# KineticHarvester_SIG_UFL_5.net
KiCad netlist of a schematic drawn in EAGLE
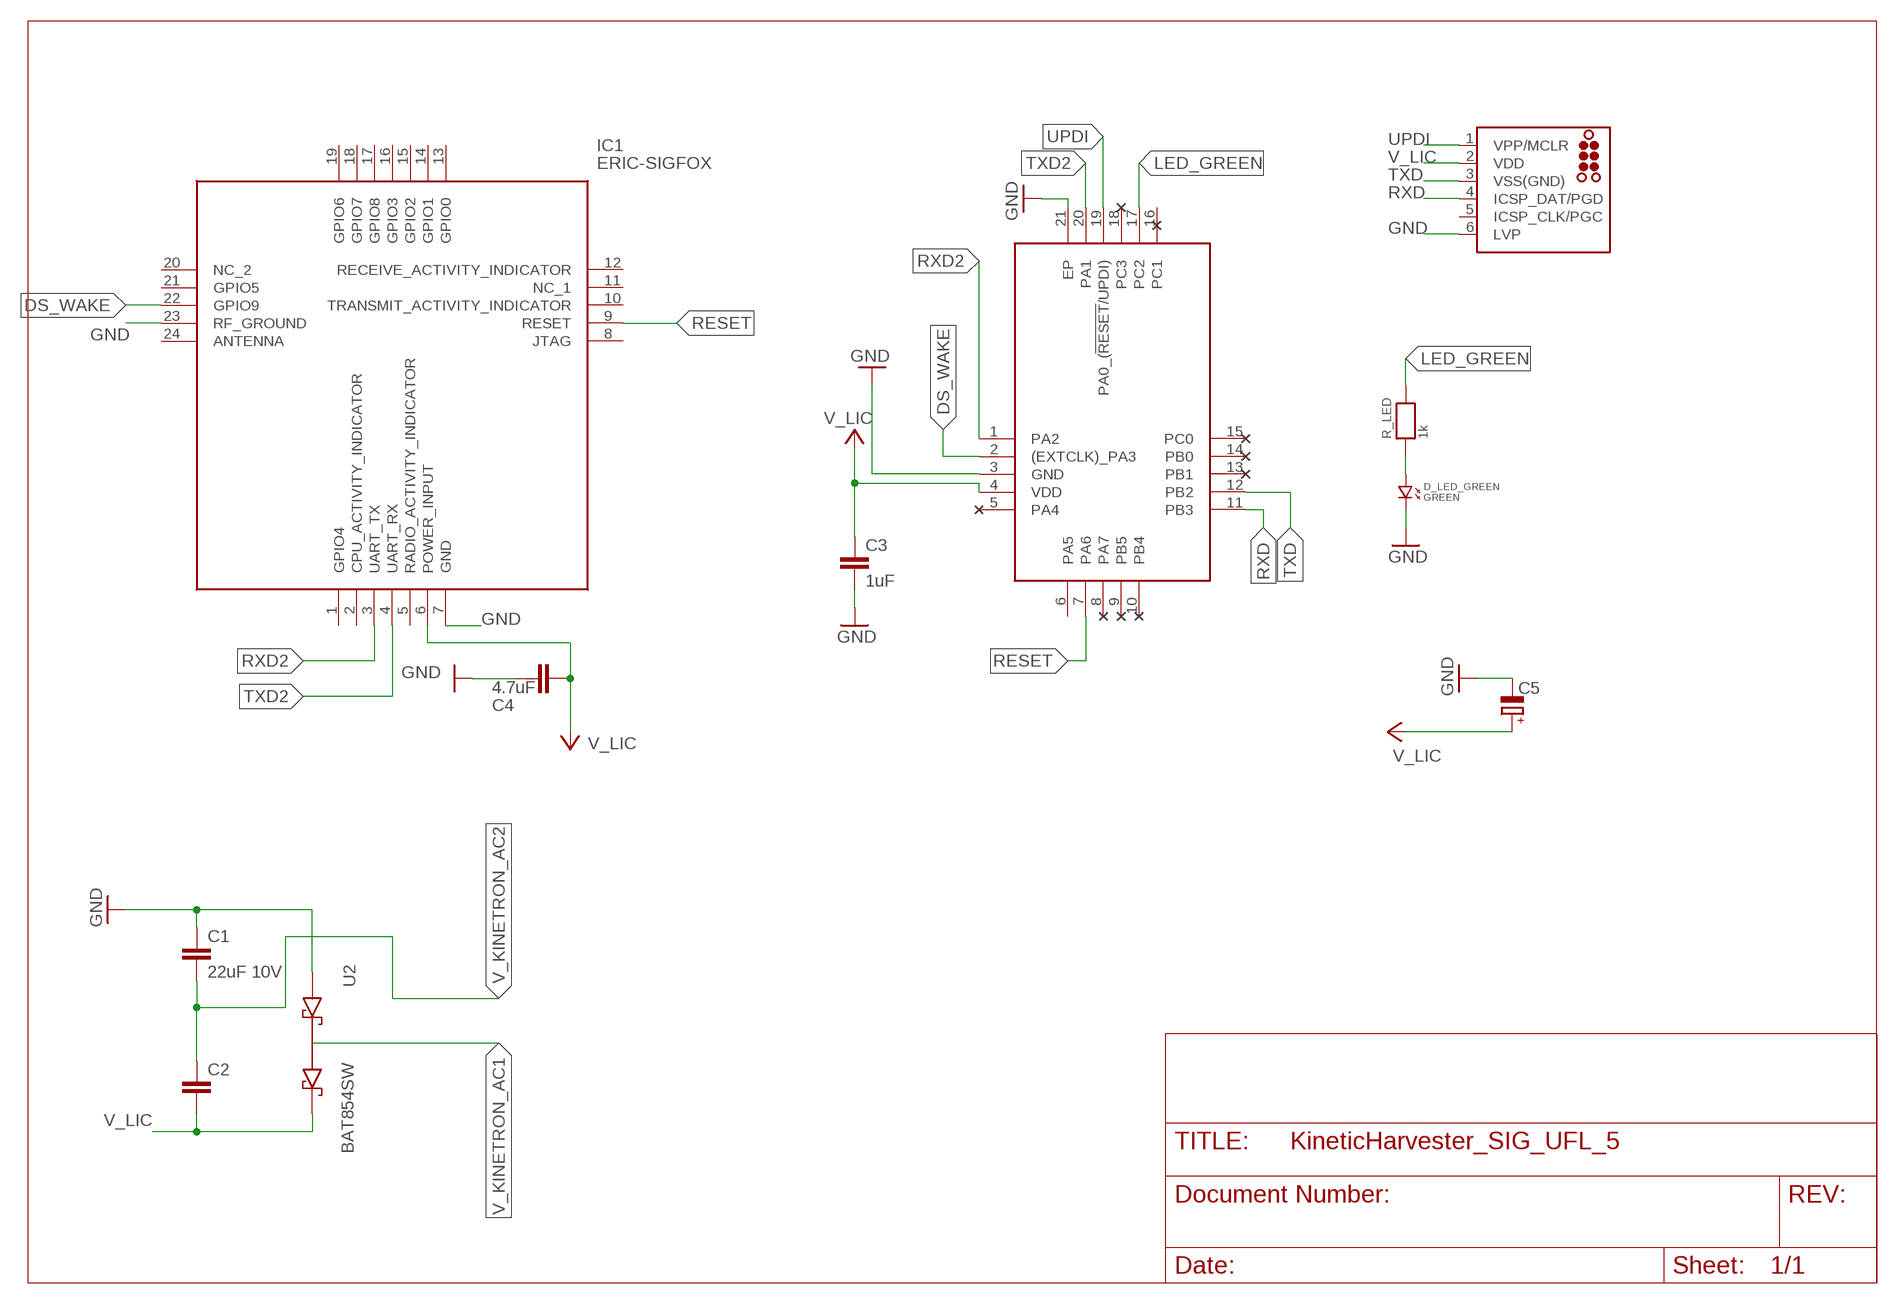
[diagram p0: schematic, sheet 1]

(export (version "E")
  (design (tool "Eeschema 10.0.6"))
  (components
    (comp (ref "ATTINY")
      (value "ATTINY1616-MFR")
      (footprint "eagle-import:QFN40P300X300X90-21N")
      (fields
        (field (name "MANUFACTURER_PART_NUMBER") "ATTINY1606-MFR")
        (field (name "MOUSER_PART_NUMBER") "556-ATTINY1606-MFR")
      )
      (libsource (lib "eagle-import") (part "ATTINY1616-MFR"))
    )
    (comp (ref "C1")
      (value "22uF 10V")
      (footprint "eagle-import:C0603")
      (fields (field (name "MF") "Murata") (field (name "MPN") "GRM188R61A226ME15D"))
      (libsource (lib "eagle-import") (part "C0603_22UF"))
    )
    (comp (ref "C2")
      (value "22uF 10V")
      (footprint "eagle-import:C0603")
      (fields (field (name "MF") "Murata") (field (name "MPN") "GRM188R61A226ME15D"))
      (libsource (lib "eagle-import") (part "C0603_22UF"))
    )
    (comp (ref "C3")
      (value "1uF")
      (footprint "eagle-import:C0402")
      (libsource (lib "eagle-import") (part "C0402_1UF"))
    )
    (comp (ref "C4")
      (value "4.7uF")
      (footprint "eagle-import:C0402")
      (fields (field (name "MF") "Murata") (field (name "MPN") "GRM155R60J475ME47D"))
      (libsource (lib "eagle-import") (part "C0402_4.7UF"))
    )
    (comp (ref "C5")
      (value "CPOL-EUE3.5-8")
      (footprint "eagle-import:E3,5-8")
      (libsource (lib "eagle-import") (part "CPOL-EUE3.5-8"))
    )
    (comp (ref "D_LED_GREEN")
      (value "GREEN")
      (footprint "eagle-import:CMONR_STANDARDPARTS_0402.LED")
      (libsource (lib "eagle-import") (part "CMONR_STANDARDPARTS_LED.0402"))
    )
    (comp (ref "IC1")
      (value "ERIC-SIGFOX")
      (footprint "eagle-import:ERICSIGFOX")
      (fields
        (field (name "MANUFACTURER_PART_NUMBER") "eRIC-SIGFOX")
        (field (name "MOUSER_PART_NUMBER") "471-ERIC-SIGFOX")
      )
      (libsource (lib "eagle-import") (part "ERIC-SIGFOX"))
    )
    (comp (ref "J1")
      (value "TC2030-MCP-NL")
      (footprint "eagle-import:TC2030-MCP-NL")
      (libsource (lib "eagle-import") (part "TC2030-MCP-NL"))
    )
    (comp (ref "R_LED")
      (value "1k")
      (footprint "eagle-import:MICROBUILDER__0402MP")
      (libsource (lib "eagle-import") (part "MICROBUILDER_RESISTOR_0402MP"))
    )
    (comp (ref "U2")
      (value "BAT854SW")
      (footprint "eagle-import:SOT323")
      (fields (field (name "MF") "NXP Semiconductors"))
      (libsource (lib "eagle-import") (part "BAT854SW"))
    )
  )
  (nets
    (net (code "1") (name "DS_WAKE") (class "Default")
      (node (ref "ATTINY") (pin "2") (pinfunction "(EXTCLK)_PA3_2") (pintype "bidirectional"))
      (node (ref "IC1") (pin "22") (pinfunction "GPIO9_22") (pintype "bidirectional"))
    )
    (net (code "2") (name "GND") (class "Default")
      (node (ref "ATTINY") (pin "21") (pinfunction "EP_21") (pintype "bidirectional"))
      (node (ref "ATTINY") (pin "3") (pinfunction "GND_3") (pintype "bidirectional"))
      (node (ref "C1") (pin "1") (pinfunction "1_1") (pintype "passive"))
      (node (ref "C3") (pin "2") (pinfunction "2_2") (pintype "passive"))
      (node (ref "C4") (pin "2") (pinfunction "2_2") (pintype "passive"))
      (node (ref "C5") (pin "-") (pinfunction "-_-") (pintype "passive"))
      (node (ref "D_LED_GREEN") (pin "P$2") (pinfunction "2_P$2") (pintype "bidirectional"))
      (node (ref "IC1") (pin "23") (pinfunction "RF_GROUND_23") (pintype "bidirectional"))
      (node (ref "IC1") (pin "7") (pinfunction "GND_7") (pintype "bidirectional"))
      (node (ref "J1") (pin "6") (pinfunction "LVP_6") (pintype "bidirectional"))
      (node (ref "U2") (pin "2") (pinfunction "PIN1_2") (pintype "passive"))
    )
    (net (code "3") (name "LED_GREEN") (class "Default")
      (node (ref "ATTINY") (pin "17") (pinfunction "PC2_17") (pintype "bidirectional"))
      (node (ref "R_LED") (pin "2") (pinfunction "2_2") (pintype "passive"))
    )
    (net (code "4") (name "Net-(D_LED_GREEN-1)") (class "Default")
      (node (ref "D_LED_GREEN") (pin "P$1") (pinfunction "1_P$1") (pintype "bidirectional"))
      (node (ref "R_LED") (pin "1") (pinfunction "1_1") (pintype "passive"))
    )
    (net (code "5") (name "RESET") (class "Default")
      (node (ref "ATTINY") (pin "7") (pinfunction "PA6_7") (pintype "bidirectional"))
      (node (ref "IC1") (pin "9") (pinfunction "RESET_9") (pintype "bidirectional"))
    )
    (net (code "6") (name "RXD") (class "Default")
      (node (ref "ATTINY") (pin "11") (pinfunction "PB3_11") (pintype "bidirectional"))
      (node (ref "J1") (pin "4") (pinfunction "ICSP_DAT/PGD_4") (pintype "bidirectional"))
    )
    (net (code "7") (name "RXD2") (class "Default")
      (node (ref "ATTINY") (pin "1") (pinfunction "PA2_1") (pintype "bidirectional"))
      (node (ref "IC1") (pin "3") (pinfunction "UART_TX_3") (pintype "bidirectional"))
    )
    (net (code "8") (name "TXD") (class "Default")
      (node (ref "ATTINY") (pin "12") (pinfunction "PB2_12") (pintype "bidirectional"))
      (node (ref "J1") (pin "3") (pinfunction "VSS(GND)_3") (pintype "power_in"))
    )
    (net (code "9") (name "TXD2") (class "Default")
      (node (ref "ATTINY") (pin "20") (pinfunction "PA1_20") (pintype "bidirectional"))
      (node (ref "IC1") (pin "4") (pinfunction "UART_RX_4") (pintype "bidirectional"))
    )
    (net (code "10") (name "UPDI") (class "Default")
      (node (ref "ATTINY") (pin "19") (pinfunction "PA0_(~{RESET}/UPDI)_19") (pintype "bidirectional"))
      (node (ref "J1") (pin "1") (pinfunction "VPP/MCLR_1") (pintype "passive"))
    )
    (net (code "11") (name "VCC") (class "Default")
      (node (ref "ATTINY") (pin "4") (pinfunction "VDD_4") (pintype "bidirectional"))
      (node (ref "C2") (pin "2") (pinfunction "2_2") (pintype "passive"))
      (node (ref "C3") (pin "1") (pinfunction "1_1") (pintype "passive"))
      (node (ref "C4") (pin "1") (pinfunction "1_1") (pintype "passive"))
      (node (ref "C5") (pin "+") (pinfunction "+_+") (pintype "passive"))
      (node (ref "IC1") (pin "6") (pinfunction "POWER_INPUT_6") (pintype "bidirectional"))
      (node (ref "J1") (pin "2") (pinfunction "VDD_2") (pintype "power_in"))
      (node (ref "U2") (pin "3") (pinfunction "PIN2_3") (pintype "passive"))
    )
    (net (code "12") (name "V_KINETRON_AC1") (class "Default")
      (node (ref "U2") (pin "1") (pinfunction "PIN3_1") (pintype "passive"))
    )
    (net (code "13") (name "V_KINETRON_AC2") (class "Default")
      (node (ref "C1") (pin "2") (pinfunction "2_2") (pintype "passive"))
      (node (ref "C2") (pin "1") (pinfunction "1_1") (pintype "passive"))
    )
    (net (code "14") (name "unconnected-(ATTINY-PA4-Pad5)") (class "Default")
      (node (ref "ATTINY") (pin "5") (pinfunction "PA4_5") (pintype "bidirectional"))
    )
    (net (code "15") (name "unconnected-(ATTINY-PA5-Pad6)") (class "Default")
      (node (ref "ATTINY") (pin "6") (pinfunction "PA5_6") (pintype "bidirectional"))
    )
    (net (code "16") (name "unconnected-(ATTINY-PA7-Pad8)") (class "Default")
      (node (ref "ATTINY") (pin "8") (pinfunction "PA7_8") (pintype "bidirectional"))
    )
    (net (code "17") (name "unconnected-(ATTINY-PB0-Pad14)") (class "Default")
      (node (ref "ATTINY") (pin "14") (pinfunction "PB0_14") (pintype "bidirectional"))
    )
    (net (code "18") (name "unconnected-(ATTINY-PB1-Pad13)") (class "Default")
      (node (ref "ATTINY") (pin "13") (pinfunction "PB1_13") (pintype "bidirectional"))
    )
    (net (code "19") (name "unconnected-(ATTINY-PB4-Pad10)") (class "Default")
      (node (ref "ATTINY") (pin "10") (pinfunction "PB4_10") (pintype "bidirectional"))
    )
    (net (code "20") (name "unconnected-(ATTINY-PB5-Pad9)") (class "Default")
      (node (ref "ATTINY") (pin "9") (pinfunction "PB5_9") (pintype "bidirectional"))
    )
    (net (code "21") (name "unconnected-(ATTINY-PC0-Pad15)") (class "Default")
      (node (ref "ATTINY") (pin "15") (pinfunction "PC0_15") (pintype "bidirectional"))
    )
    (net (code "22") (name "unconnected-(ATTINY-PC1-Pad16)") (class "Default")
      (node (ref "ATTINY") (pin "16") (pinfunction "PC1_16") (pintype "bidirectional"))
    )
    (net (code "23") (name "unconnected-(ATTINY-PC3-Pad18)") (class "Default")
      (node (ref "ATTINY") (pin "18") (pinfunction "PC3_18") (pintype "bidirectional"))
    )
    (net (code "24") (name "unconnected-(IC1-ANTENNA-Pad24)") (class "Default")
      (node (ref "IC1") (pin "24") (pinfunction "ANTENNA_24") (pintype "bidirectional"))
    )
    (net (code "25") (name "unconnected-(IC1-CPU_ACTIVITY_INDICATOR-Pad2)") (class "Default")
      (node (ref "IC1") (pin "2") (pinfunction "CPU_ACTIVITY_INDICATOR_2") (pintype "bidirectional"))
    )
    (net (code "26") (name "unconnected-(IC1-GPIO0-Pad13)") (class "Default")
      (node (ref "IC1") (pin "13") (pinfunction "GPIO0_13") (pintype "bidirectional"))
    )
    (net (code "27") (name "unconnected-(IC1-GPIO1-Pad14)") (class "Default")
      (node (ref "IC1") (pin "14") (pinfunction "GPIO1_14") (pintype "bidirectional"))
    )
    (net (code "28") (name "unconnected-(IC1-GPIO2-Pad15)") (class "Default")
      (node (ref "IC1") (pin "15") (pinfunction "GPIO2_15") (pintype "bidirectional"))
    )
    (net (code "29") (name "unconnected-(IC1-GPIO3-Pad16)") (class "Default")
      (node (ref "IC1") (pin "16") (pinfunction "GPIO3_16") (pintype "bidirectional"))
    )
    (net (code "30") (name "unconnected-(IC1-GPIO4-Pad1)") (class "Default")
      (node (ref "IC1") (pin "1") (pinfunction "GPIO4_1") (pintype "bidirectional"))
    )
    (net (code "31") (name "unconnected-(IC1-GPIO5-Pad21)") (class "Default")
      (node (ref "IC1") (pin "21") (pinfunction "GPIO5_21") (pintype "bidirectional"))
    )
    (net (code "32") (name "unconnected-(IC1-GPIO6-Pad19)") (class "Default")
      (node (ref "IC1") (pin "19") (pinfunction "GPIO6_19") (pintype "bidirectional"))
    )
    (net (code "33") (name "unconnected-(IC1-GPIO7-Pad18)") (class "Default")
      (node (ref "IC1") (pin "18") (pinfunction "GPIO7_18") (pintype "bidirectional"))
    )
    (net (code "34") (name "unconnected-(IC1-GPIO8-Pad17)") (class "Default")
      (node (ref "IC1") (pin "17") (pinfunction "GPIO8_17") (pintype "bidirectional"))
    )
    (net (code "35") (name "unconnected-(IC1-JTAG-Pad8)") (class "Default")
      (node (ref "IC1") (pin "8") (pinfunction "JTAG_8") (pintype "bidirectional"))
    )
    (net (code "36") (name "unconnected-(IC1-NC_1-Pad11)") (class "Default")
      (node (ref "IC1") (pin "11") (pinfunction "NC_1_11") (pintype "bidirectional"))
    )
    (net (code "37") (name "unconnected-(IC1-NC_2-Pad20)") (class "Default")
      (node (ref "IC1") (pin "20") (pinfunction "NC_2_20") (pintype "bidirectional"))
    )
    (net (code "38") (name "unconnected-(IC1-RADIO_ACTIVITY_INDICATOR-Pad5)") (class "Default")
      (node (ref "IC1") (pin "5") (pinfunction "RADIO_ACTIVITY_INDICATOR_5") (pintype "bidirectional"))
    )
    (net (code "39") (name "unconnected-(IC1-RECEIVE_ACTIVITY_INDICATOR-Pad12)") (class "Default")
      (node (ref "IC1") (pin "12") (pinfunction "RECEIVE_ACTIVITY_INDICATOR_12") (pintype "bidirectional"))
    )
    (net (code "40") (name "unconnected-(IC1-TRANSMIT_ACTIVITY_INDICATOR-Pad10)") (class "Default")
      (node (ref "IC1") (pin "10") (pinfunction "TRANSMIT_ACTIVITY_INDICATOR_10") (pintype "bidirectional"))
    )
    (net (code "41") (name "unconnected-(J1-ICSP_CLK{slash}PGC-Pad5)") (class "Default")
      (node (ref "J1") (pin "5") (pinfunction "ICSP_CLK/PGC_5") (pintype "output"))
    )
  )
)
